# main_board_schem.net
KiCad netlist of a schematic drawn in Altium Designer
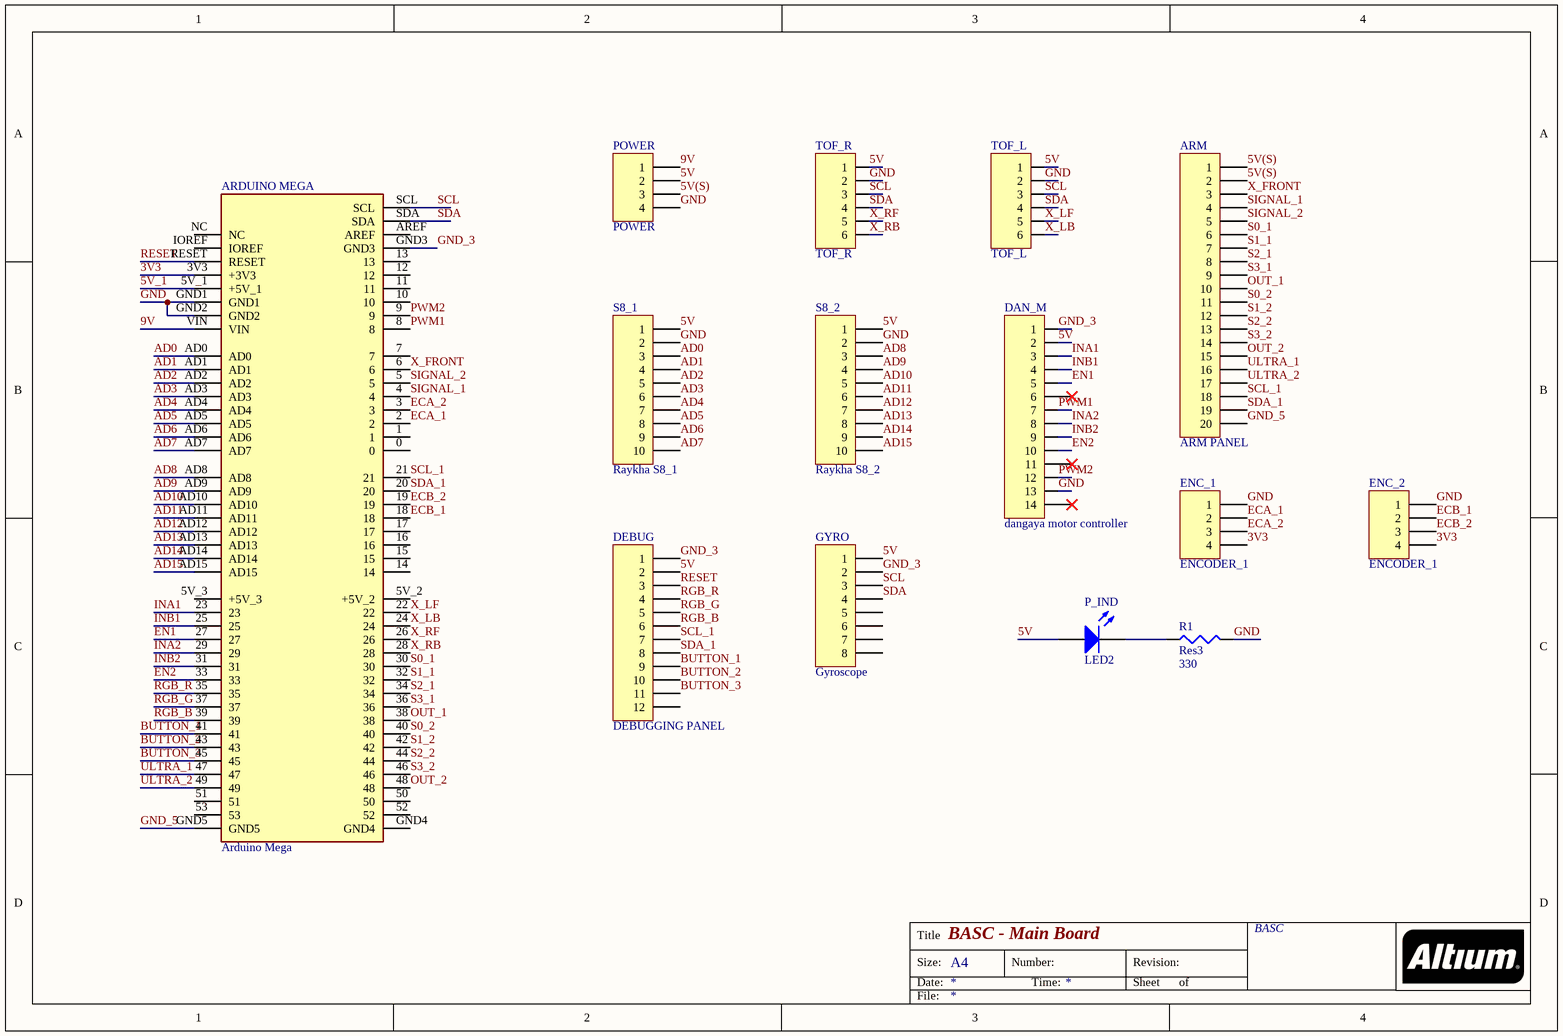
[diagram p0: main_board_schem.SchDoc]

(export (version "E")
  (design (tool "Eeschema 10.0.6"))
  (components
    (comp (ref "ARDUINO MEGA")
      (value "Arduino Mega")
      (footprint "ARDUINO_A000067")
      (description "ATmega2560 Arduino Mega2560 AVRÂ® ATmega AVR MCU 8-Bit Embedded Evaluation Board")
      (fields (field (name "MP") "A000067") (field (name "MF") "Arduino"))
      (libsource (lib "arduino_mega") (part "A000067"))
    )
    (comp (ref "ARM")
      (value "ARM PANEL")
      (footprint "HDR2X10")
      (description "Header, 20-Pin")
      (fields (field (name "PUBLISHER") "Altium Limited"))
      (libsource (lib "Miscellaneous Connectors") (part "Header 20"))
    )
    (comp (ref "DAN_M")
      (value "dangaya motor controller")
      (footprint "HDR1X14")
      (description "Header, 14-Pin")
      (fields (field (name "PUBLISHER") "Altium Limited"))
      (libsource (lib "Miscellaneous Connectors") (part "Header 14"))
    )
    (comp (ref "DEBUG")
      (value "DEBUGGING PANEL")
      (footprint "HDR1X12")
      (description "Header, 12-Pin")
      (fields (field (name "PUBLISHER") "Altium Limited"))
      (libsource (lib "Miscellaneous Connectors") (part "Header 12"))
    )
    (comp (ref "ENC_1")
      (value "ENCODER_1")
      (footprint "HDR1X4")
      (description "Header, 4-Pin")
      (fields (field (name "PUBLISHER") "Altium Limited"))
      (libsource (lib "Miscellaneous Connectors") (part "Header 4"))
    )
    (comp (ref "ENC_2")
      (value "ENCODER_1")
      (footprint "HDR1X4")
      (description "Header, 4-Pin")
      (fields (field (name "PUBLISHER") "Altium Limited"))
      (libsource (lib "Miscellaneous Connectors") (part "Header 4"))
    )
    (comp (ref "GYRO")
      (value "Gyroscope")
      (footprint "HDR1X8")
      (description "Header, 8-Pin")
      (fields (field (name "PUBLISHER") "Altium Limited"))
      (libsource (lib "Miscellaneous Connectors") (part "Header 8"))
    )
    (comp (ref "POWER")
      (value "POWER")
      (footprint "HDR1X4")
      (description "Header, 4-Pin")
      (fields (field (name "PUBLISHER") "Altium Limited"))
      (libsource (lib "Miscellaneous Connectors") (part "Header 4"))
    )
    (comp (ref "P_IND")
      (value "LED2")
      (footprint "3.2X1.6X1.1")
      (description "Typical RED, GREEN, YELLOW, AMBER GaAs LED")
      (fields (field (name "PUBLISHER") "Altium Limited"))
      (libsource (lib "Miscellaneous Devices") (part "LED2"))
    )
    (comp (ref "R1")
      (value "Res3")
      (footprint "RESC3216X75N")
      (description "Resistor")
      (fields (field (name "ALTIUM_VALUE") "330") (field (name "PUBLISHER") "Altium Limited"))
      (libsource (lib "Miscellaneous Devices") (part "Res3"))
    )
    (comp (ref "S8_1")
      (value "Raykha S8_1")
      (footprint "HDR1X10")
      (description "Header, 10-Pin")
      (fields (field (name "PUBLISHER") "Altium Limited"))
      (libsource (lib "Miscellaneous Connectors") (part "Header 10"))
    )
    (comp (ref "S8_2")
      (value "Raykha S8_2")
      (footprint "HDR1X10")
      (description "Header, 10-Pin")
      (fields (field (name "PUBLISHER") "Altium Limited"))
      (libsource (lib "Miscellaneous Connectors") (part "Header 10"))
    )
    (comp (ref "TOF_L")
      (value "TOF_L")
      (footprint "HDR1X6")
      (description "Header, 6-Pin")
      (fields (field (name "PUBLISHER") "Altium Limited"))
      (libsource (lib "Miscellaneous Connectors") (part "Header 6"))
    )
    (comp (ref "TOF_R")
      (value "TOF_R")
      (footprint "HDR1X6")
      (description "Header, 6-Pin")
      (fields (field (name "PUBLISHER") "Altium Limited"))
      (libsource (lib "Miscellaneous Connectors") (part "Header 6"))
    )
  )
  (nets
    (net (code "1") (name "/3V3") (class "Default")
      (node (ref "ARDUINO MEGA") (pin "3V3") (pinfunction "+3V3_3V3") (pintype "passive"))
      (node (ref "ENC_1") (pin "4") (pinfunction "4_4") (pintype "passive"))
      (node (ref "ENC_2") (pin "4") (pinfunction "4_4") (pintype "passive"))
    )
    (net (code "2") (name "/5V") (class "Default")
      (node (ref "DAN_M") (pin "2") (pinfunction "2_2") (pintype "passive"))
      (node (ref "DEBUG") (pin "2") (pinfunction "2_2") (pintype "passive"))
      (node (ref "GYRO") (pin "1") (pinfunction "1_1") (pintype "passive"))
      (node (ref "POWER") (pin "2") (pinfunction "2_2") (pintype "passive"))
      (node (ref "P_IND") (pin "1") (pinfunction "A_1") (pintype "passive"))
      (node (ref "S8_1") (pin "1") (pinfunction "1_1") (pintype "passive"))
      (node (ref "S8_2") (pin "1") (pinfunction "1_1") (pintype "passive"))
      (node (ref "TOF_L") (pin "1") (pinfunction "1_1") (pintype "passive"))
      (node (ref "TOF_R") (pin "1") (pinfunction "1_1") (pintype "passive"))
    )
    (net (code "3") (name "/5V(S)") (class "Default")
      (node (ref "ARM") (pin "1") (pinfunction "1_1") (pintype "passive"))
      (node (ref "ARM") (pin "2") (pinfunction "2_2") (pintype "passive"))
      (node (ref "POWER") (pin "3") (pinfunction "3_3") (pintype "passive"))
    )
    (net (code "4") (name "/5V_1") (class "Default")
      (node (ref "ARDUINO MEGA") (pin "5V_1") (pinfunction "+5V_1_5V_1") (pintype "passive"))
    )
    (net (code "5") (name "/9V") (class "Default")
      (node (ref "ARDUINO MEGA") (pin "VIN") (pinfunction "VIN_VIN") (pintype "passive"))
      (node (ref "POWER") (pin "1") (pinfunction "1_1") (pintype "passive"))
    )
    (net (code "6") (name "/AD0") (class "Default")
      (node (ref "ARDUINO MEGA") (pin "AD0") (pinfunction "AD0_AD0") (pintype "passive"))
      (node (ref "S8_1") (pin "3") (pinfunction "3_3") (pintype "passive"))
    )
    (net (code "7") (name "/AD1") (class "Default")
      (node (ref "ARDUINO MEGA") (pin "AD1") (pinfunction "AD1_AD1") (pintype "passive"))
      (node (ref "S8_1") (pin "4") (pinfunction "4_4") (pintype "passive"))
    )
    (net (code "8") (name "/AD2") (class "Default")
      (node (ref "ARDUINO MEGA") (pin "AD2") (pinfunction "AD2_AD2") (pintype "passive"))
      (node (ref "S8_1") (pin "5") (pinfunction "5_5") (pintype "passive"))
    )
    (net (code "9") (name "/AD3") (class "Default")
      (node (ref "ARDUINO MEGA") (pin "AD3") (pinfunction "AD3_AD3") (pintype "passive"))
      (node (ref "S8_1") (pin "6") (pinfunction "6_6") (pintype "passive"))
    )
    (net (code "10") (name "/AD4") (class "Default")
      (node (ref "ARDUINO MEGA") (pin "AD4") (pinfunction "AD4_AD4") (pintype "passive"))
      (node (ref "S8_1") (pin "7") (pinfunction "7_7") (pintype "passive"))
    )
    (net (code "11") (name "/AD5") (class "Default")
      (node (ref "ARDUINO MEGA") (pin "AD5") (pinfunction "AD5_AD5") (pintype "passive"))
      (node (ref "S8_1") (pin "8") (pinfunction "8_8") (pintype "passive"))
    )
    (net (code "12") (name "/AD6") (class "Default")
      (node (ref "ARDUINO MEGA") (pin "AD6") (pinfunction "AD6_AD6") (pintype "passive"))
      (node (ref "S8_1") (pin "9") (pinfunction "9_9") (pintype "passive"))
    )
    (net (code "13") (name "/AD7") (class "Default")
      (node (ref "ARDUINO MEGA") (pin "AD7") (pinfunction "AD7_AD7") (pintype "passive"))
      (node (ref "S8_1") (pin "10") (pinfunction "10_10") (pintype "passive"))
    )
    (net (code "14") (name "/AD8") (class "Default")
      (node (ref "ARDUINO MEGA") (pin "AD8") (pinfunction "AD8_AD8") (pintype "passive"))
      (node (ref "S8_2") (pin "3") (pinfunction "3_3") (pintype "passive"))
    )
    (net (code "15") (name "/AD9") (class "Default")
      (node (ref "ARDUINO MEGA") (pin "AD9") (pinfunction "AD9_AD9") (pintype "passive"))
      (node (ref "S8_2") (pin "4") (pinfunction "4_4") (pintype "passive"))
    )
    (net (code "16") (name "/AD10") (class "Default")
      (node (ref "ARDUINO MEGA") (pin "AD10") (pinfunction "AD10_AD10") (pintype "passive"))
      (node (ref "S8_2") (pin "5") (pinfunction "5_5") (pintype "passive"))
    )
    (net (code "17") (name "/AD11") (class "Default")
      (node (ref "ARDUINO MEGA") (pin "AD11") (pinfunction "AD11_AD11") (pintype "passive"))
      (node (ref "S8_2") (pin "6") (pinfunction "6_6") (pintype "passive"))
    )
    (net (code "18") (name "/AD12") (class "Default")
      (node (ref "ARDUINO MEGA") (pin "AD12") (pinfunction "AD12_AD12") (pintype "passive"))
      (node (ref "S8_2") (pin "7") (pinfunction "7_7") (pintype "passive"))
    )
    (net (code "19") (name "/AD13") (class "Default")
      (node (ref "ARDUINO MEGA") (pin "AD13") (pinfunction "AD13_AD13") (pintype "passive"))
      (node (ref "S8_2") (pin "8") (pinfunction "8_8") (pintype "passive"))
    )
    (net (code "20") (name "/AD14") (class "Default")
      (node (ref "ARDUINO MEGA") (pin "AD14") (pinfunction "AD14_AD14") (pintype "passive"))
      (node (ref "S8_2") (pin "9") (pinfunction "9_9") (pintype "passive"))
    )
    (net (code "21") (name "/AD15") (class "Default")
      (node (ref "ARDUINO MEGA") (pin "AD15") (pinfunction "AD15_AD15") (pintype "passive"))
      (node (ref "S8_2") (pin "10") (pinfunction "10_10") (pintype "passive"))
    )
    (net (code "22") (name "/BUTTON_1") (class "Default")
      (node (ref "ARDUINO MEGA") (pin "41") (pinfunction "41_41") (pintype "passive"))
      (node (ref "DEBUG") (pin "9") (pinfunction "9_9") (pintype "passive"))
    )
    (net (code "23") (name "/BUTTON_2") (class "Default")
      (node (ref "ARDUINO MEGA") (pin "43") (pinfunction "43_43") (pintype "passive"))
      (node (ref "DEBUG") (pin "10") (pinfunction "10_10") (pintype "passive"))
    )
    (net (code "24") (name "/BUTTON_3") (class "Default")
      (node (ref "ARDUINO MEGA") (pin "45") (pinfunction "45_45") (pintype "passive"))
      (node (ref "DEBUG") (pin "11") (pinfunction "11_11") (pintype "passive"))
    )
    (net (code "25") (name "/ECA_1") (class "Default")
      (node (ref "ARDUINO MEGA") (pin "2") (pinfunction "2_2") (pintype "passive"))
      (node (ref "ENC_1") (pin "2") (pinfunction "2_2") (pintype "passive"))
    )
    (net (code "26") (name "/ECA_2") (class "Default")
      (node (ref "ARDUINO MEGA") (pin "3") (pinfunction "3_3") (pintype "passive"))
      (node (ref "ENC_1") (pin "3") (pinfunction "3_3") (pintype "passive"))
    )
    (net (code "27") (name "/ECB_1") (class "Default")
      (node (ref "ARDUINO MEGA") (pin "18") (pinfunction "18_18") (pintype "passive"))
      (node (ref "ENC_2") (pin "2") (pinfunction "2_2") (pintype "passive"))
    )
    (net (code "28") (name "/ECB_2") (class "Default")
      (node (ref "ARDUINO MEGA") (pin "19") (pinfunction "19_19") (pintype "passive"))
      (node (ref "ENC_2") (pin "3") (pinfunction "3_3") (pintype "passive"))
    )
    (net (code "29") (name "/EN1") (class "Default")
      (node (ref "ARDUINO MEGA") (pin "27") (pinfunction "27_27") (pintype "passive"))
      (node (ref "DAN_M") (pin "5") (pinfunction "5_5") (pintype "passive"))
    )
    (net (code "30") (name "/EN2") (class "Default")
      (node (ref "ARDUINO MEGA") (pin "33") (pinfunction "33_33") (pintype "passive"))
      (node (ref "DAN_M") (pin "10") (pinfunction "10_10") (pintype "passive"))
    )
    (net (code "31") (name "/GND") (class "Default")
      (node (ref "ARDUINO MEGA") (pin "GND1") (pinfunction "GND1_GND1") (pintype "passive"))
      (node (ref "ARDUINO MEGA") (pin "GND2") (pinfunction "GND2_GND2") (pintype "passive"))
      (node (ref "DAN_M") (pin "13") (pinfunction "13_13") (pintype "passive"))
      (node (ref "ENC_1") (pin "1") (pinfunction "1_1") (pintype "passive"))
      (node (ref "ENC_2") (pin "1") (pinfunction "1_1") (pintype "passive"))
      (node (ref "POWER") (pin "4") (pinfunction "4_4") (pintype "passive"))
      (node (ref "R1") (pin "2") (pinfunction "2_2") (pintype "passive"))
      (node (ref "S8_1") (pin "2") (pinfunction "2_2") (pintype "passive"))
      (node (ref "S8_2") (pin "2") (pinfunction "2_2") (pintype "passive"))
      (node (ref "TOF_L") (pin "2") (pinfunction "2_2") (pintype "passive"))
      (node (ref "TOF_R") (pin "2") (pinfunction "2_2") (pintype "passive"))
    )
    (net (code "32") (name "/GND_3") (class "Default")
      (node (ref "ARDUINO MEGA") (pin "GND3") (pinfunction "GND3_GND3") (pintype "passive"))
      (node (ref "DAN_M") (pin "1") (pinfunction "1_1") (pintype "passive"))
      (node (ref "DEBUG") (pin "1") (pinfunction "1_1") (pintype "passive"))
      (node (ref "GYRO") (pin "2") (pinfunction "2_2") (pintype "passive"))
    )
    (net (code "33") (name "/GND_5") (class "Default")
      (node (ref "ARDUINO MEGA") (pin "GND5") (pinfunction "GND5_GND5") (pintype "passive"))
      (node (ref "ARM") (pin "20") (pinfunction "20_20") (pintype "passive"))
    )
    (net (code "34") (name "/INA1") (class "Default")
      (node (ref "ARDUINO MEGA") (pin "23") (pinfunction "23_23") (pintype "passive"))
      (node (ref "DAN_M") (pin "3") (pinfunction "3_3") (pintype "passive"))
    )
    (net (code "35") (name "/INA2") (class "Default")
      (node (ref "ARDUINO MEGA") (pin "29") (pinfunction "29_29") (pintype "passive"))
      (node (ref "DAN_M") (pin "8") (pinfunction "8_8") (pintype "passive"))
    )
    (net (code "36") (name "/INB1") (class "Default")
      (node (ref "ARDUINO MEGA") (pin "25") (pinfunction "25_25") (pintype "passive"))
      (node (ref "DAN_M") (pin "4") (pinfunction "4_4") (pintype "passive"))
    )
    (net (code "37") (name "/INB2") (class "Default")
      (node (ref "ARDUINO MEGA") (pin "31") (pinfunction "31_31") (pintype "passive"))
      (node (ref "DAN_M") (pin "9") (pinfunction "9_9") (pintype "passive"))
    )
    (net (code "38") (name "/OUT_1") (class "Default")
      (node (ref "ARDUINO MEGA") (pin "38") (pinfunction "38_38") (pintype "passive"))
      (node (ref "ARM") (pin "10") (pinfunction "10_10") (pintype "passive"))
    )
    (net (code "39") (name "/OUT_2") (class "Default")
      (node (ref "ARDUINO MEGA") (pin "48") (pinfunction "48_48") (pintype "passive"))
      (node (ref "ARM") (pin "15") (pinfunction "15_15") (pintype "passive"))
    )
    (net (code "40") (name "/PWM1") (class "Default")
      (node (ref "ARDUINO MEGA") (pin "8") (pinfunction "8_8") (pintype "passive"))
      (node (ref "DAN_M") (pin "7") (pinfunction "7_7") (pintype "passive"))
    )
    (net (code "41") (name "/PWM2") (class "Default")
      (node (ref "ARDUINO MEGA") (pin "9") (pinfunction "9_9") (pintype "passive"))
      (node (ref "DAN_M") (pin "12") (pinfunction "12_12") (pintype "passive"))
    )
    (net (code "42") (name "/RESET") (class "Default")
      (node (ref "ARDUINO MEGA") (pin "RESET") (pinfunction "RESET_RESET") (pintype "passive"))
      (node (ref "DEBUG") (pin "3") (pinfunction "3_3") (pintype "passive"))
    )
    (net (code "43") (name "/RGB_B") (class "Default")
      (node (ref "ARDUINO MEGA") (pin "39") (pinfunction "39_39") (pintype "passive"))
      (node (ref "DEBUG") (pin "6") (pinfunction "6_6") (pintype "passive"))
    )
    (net (code "44") (name "/RGB_G") (class "Default")
      (node (ref "ARDUINO MEGA") (pin "37") (pinfunction "37_37") (pintype "passive"))
      (node (ref "DEBUG") (pin "5") (pinfunction "5_5") (pintype "passive"))
    )
    (net (code "45") (name "/RGB_R") (class "Default")
      (node (ref "ARDUINO MEGA") (pin "35") (pinfunction "35_35") (pintype "passive"))
      (node (ref "DEBUG") (pin "4") (pinfunction "4_4") (pintype "passive"))
    )
    (net (code "46") (name "/S0_1") (class "Default")
      (node (ref "ARDUINO MEGA") (pin "30") (pinfunction "30_30") (pintype "passive"))
      (node (ref "ARM") (pin "6") (pinfunction "6_6") (pintype "passive"))
    )
    (net (code "47") (name "/S0_2") (class "Default")
      (node (ref "ARDUINO MEGA") (pin "40") (pinfunction "40_40") (pintype "passive"))
      (node (ref "ARM") (pin "11") (pinfunction "11_11") (pintype "passive"))
    )
    (net (code "48") (name "/S1_1") (class "Default")
      (node (ref "ARDUINO MEGA") (pin "32") (pinfunction "32_32") (pintype "passive"))
      (node (ref "ARM") (pin "7") (pinfunction "7_7") (pintype "passive"))
    )
    (net (code "49") (name "/S1_2") (class "Default")
      (node (ref "ARDUINO MEGA") (pin "42") (pinfunction "42_42") (pintype "passive"))
      (node (ref "ARM") (pin "12") (pinfunction "12_12") (pintype "passive"))
    )
    (net (code "50") (name "/S2_1") (class "Default")
      (node (ref "ARDUINO MEGA") (pin "34") (pinfunction "34_34") (pintype "passive"))
      (node (ref "ARM") (pin "8") (pinfunction "8_8") (pintype "passive"))
    )
    (net (code "51") (name "/S2_2") (class "Default")
      (node (ref "ARDUINO MEGA") (pin "44") (pinfunction "44_44") (pintype "passive"))
      (node (ref "ARM") (pin "13") (pinfunction "13_13") (pintype "passive"))
    )
    (net (code "52") (name "/S3_1") (class "Default")
      (node (ref "ARDUINO MEGA") (pin "36") (pinfunction "36_36") (pintype "passive"))
      (node (ref "ARM") (pin "9") (pinfunction "9_9") (pintype "passive"))
    )
    (net (code "53") (name "/S3_2") (class "Default")
      (node (ref "ARDUINO MEGA") (pin "46") (pinfunction "46_46") (pintype "passive"))
      (node (ref "ARM") (pin "14") (pinfunction "14_14") (pintype "passive"))
    )
    (net (code "54") (name "/SCL") (class "Default")
      (node (ref "ARDUINO MEGA") (pin "SCL") (pinfunction "SCL_SCL") (pintype "passive"))
      (node (ref "GYRO") (pin "3") (pinfunction "3_3") (pintype "passive"))
      (node (ref "TOF_L") (pin "3") (pinfunction "3_3") (pintype "passive"))
      (node (ref "TOF_R") (pin "3") (pinfunction "3_3") (pintype "passive"))
    )
    (net (code "55") (name "/SCL_1") (class "Default")
      (node (ref "ARDUINO MEGA") (pin "21") (pinfunction "21_21") (pintype "passive"))
      (node (ref "ARM") (pin "18") (pinfunction "18_18") (pintype "passive"))
      (node (ref "DEBUG") (pin "7") (pinfunction "7_7") (pintype "passive"))
    )
    (net (code "56") (name "/SDA") (class "Default")
      (node (ref "ARDUINO MEGA") (pin "SDA") (pinfunction "SDA_SDA") (pintype "passive"))
      (node (ref "GYRO") (pin "4") (pinfunction "4_4") (pintype "passive"))
      (node (ref "TOF_L") (pin "4") (pinfunction "4_4") (pintype "passive"))
      (node (ref "TOF_R") (pin "4") (pinfunction "4_4") (pintype "passive"))
    )
    (net (code "57") (name "/SDA_1") (class "Default")
      (node (ref "ARDUINO MEGA") (pin "20") (pinfunction "20_20") (pintype "passive"))
      (node (ref "ARM") (pin "19") (pinfunction "19_19") (pintype "passive"))
      (node (ref "DEBUG") (pin "8") (pinfunction "8_8") (pintype "passive"))
    )
    (net (code "58") (name "/SIGNAL_1") (class "Default")
      (node (ref "ARDUINO MEGA") (pin "4") (pinfunction "4_4") (pintype "passive"))
      (node (ref "ARM") (pin "4") (pinfunction "4_4") (pintype "passive"))
    )
    (net (code "59") (name "/SIGNAL_2") (class "Default")
      (node (ref "ARDUINO MEGA") (pin "5") (pinfunction "5_5") (pintype "passive"))
      (node (ref "ARM") (pin "5") (pinfunction "5_5") (pintype "passive"))
    )
    (net (code "60") (name "/ULTRA_1") (class "Default")
      (node (ref "ARDUINO MEGA") (pin "47") (pinfunction "47_47") (pintype "passive"))
      (node (ref "ARM") (pin "16") (pinfunction "16_16") (pintype "passive"))
    )
    (net (code "61") (name "/ULTRA_2") (class "Default")
      (node (ref "ARDUINO MEGA") (pin "49") (pinfunction "49_49") (pintype "passive"))
      (node (ref "ARM") (pin "17") (pinfunction "17_17") (pintype "passive"))
    )
    (net (code "62") (name "/X_FRONT") (class "Default")
      (node (ref "ARDUINO MEGA") (pin "6") (pinfunction "6_6") (pintype "passive"))
      (node (ref "ARM") (pin "3") (pinfunction "3_3") (pintype "passive"))
    )
    (net (code "63") (name "/X_LB") (class "Default")
      (node (ref "ARDUINO MEGA") (pin "24") (pinfunction "24_24") (pintype "passive"))
      (node (ref "TOF_L") (pin "6") (pinfunction "6_6") (pintype "passive"))
    )
    (net (code "64") (name "/X_LF") (class "Default")
      (node (ref "ARDUINO MEGA") (pin "22") (pinfunction "22_22") (pintype "passive"))
      (node (ref "TOF_L") (pin "5") (pinfunction "5_5") (pintype "passive"))
    )
    (net (code "65") (name "/X_RB") (class "Default")
      (node (ref "ARDUINO MEGA") (pin "28") (pinfunction "28_28") (pintype "passive"))
      (node (ref "TOF_R") (pin "6") (pinfunction "6_6") (pintype "passive"))
    )
    (net (code "66") (name "/X_RF") (class "Default")
      (node (ref "ARDUINO MEGA") (pin "26") (pinfunction "26_26") (pintype "passive"))
      (node (ref "TOF_R") (pin "5") (pinfunction "5_5") (pintype "passive"))
    )
    (net (code "67") (name "Net-(P_IND-K)") (class "Default")
      (node (ref "P_IND") (pin "2") (pinfunction "K_2") (pintype "passive"))
      (node (ref "R1") (pin "1") (pinfunction "1_1") (pintype "passive"))
    )
    (net (code "68") (name "unconnected-(ARDUINO MEGA-+5V_2-Pad5V_2)") (class "Default")
      (node (ref "ARDUINO MEGA") (pin "5V_2") (pinfunction "+5V_2_5V_2") (pintype "passive"))
    )
    (net (code "69") (name "unconnected-(ARDUINO MEGA-+5V_3-Pad5V_3)") (class "Default")
      (node (ref "ARDUINO MEGA") (pin "5V_3") (pinfunction "+5V_3_5V_3") (pintype "passive"))
    )
    (net (code "70") (name "unconnected-(ARDUINO MEGA-Pad0)") (class "Default")
      (node (ref "ARDUINO MEGA") (pin "0") (pinfunction "0_0") (pintype "passive"))
    )
    (net (code "71") (name "unconnected-(ARDUINO MEGA-Pad1)") (class "Default")
      (node (ref "ARDUINO MEGA") (pin "1") (pinfunction "1_1") (pintype "passive"))
    )
    (net (code "72") (name "unconnected-(ARDUINO MEGA-Pad7)") (class "Default")
      (node (ref "ARDUINO MEGA") (pin "7") (pinfunction "7_7") (pintype "passive"))
    )
    (net (code "73") (name "unconnected-(ARDUINO MEGA-Pad10)") (class "Default")
      (node (ref "ARDUINO MEGA") (pin "10") (pinfunction "10_10") (pintype "passive"))
    )
    (net (code "74") (name "unconnected-(ARDUINO MEGA-Pad11)") (class "Default")
      (node (ref "ARDUINO MEGA") (pin "11") (pinfunction "11_11") (pintype "passive"))
    )
    (net (code "75") (name "unconnected-(ARDUINO MEGA-Pad12)") (class "Default")
      (node (ref "ARDUINO MEGA") (pin "12") (pinfunction "12_12") (pintype "passive"))
    )
    (net (code "76") (name "unconnected-(ARDUINO MEGA-Pad13)") (class "Default")
      (node (ref "ARDUINO MEGA") (pin "13") (pinfunction "13_13") (pintype "passive"))
    )
    (net (code "77") (name "unconnected-(ARDUINO MEGA-Pad14)") (class "Default")
      (node (ref "ARDUINO MEGA") (pin "14") (pinfunction "14_14") (pintype "passive"))
    )
    (net (code "78") (name "unconnected-(ARDUINO MEGA-Pad15)") (class "Default")
      (node (ref "ARDUINO MEGA") (pin "15") (pinfunction "15_15") (pintype "passive"))
    )
    (net (code "79") (name "unconnected-(ARDUINO MEGA-Pad16)") (class "Default")
      (node (ref "ARDUINO MEGA") (pin "16") (pinfunction "16_16") (pintype "passive"))
    )
    (net (code "80") (name "unconnected-(ARDUINO MEGA-Pad17)") (class "Default")
      (node (ref "ARDUINO MEGA") (pin "17") (pinfunction "17_17") (pintype "passive"))
    )
    (net (code "81") (name "unconnected-(ARDUINO MEGA-Pad50)") (class "Default")
      (node (ref "ARDUINO MEGA") (pin "50") (pinfunction "50_50") (pintype "passive"))
    )
    (net (code "82") (name "unconnected-(ARDUINO MEGA-Pad51)") (class "Default")
      (node (ref "ARDUINO MEGA") (pin "51") (pinfunction "51_51") (pintype "passive"))
    )
    (net (code "83") (name "unconnected-(ARDUINO MEGA-Pad52)") (class "Default")
      (node (ref "ARDUINO MEGA") (pin "52") (pinfunction "52_52") (pintype "passive"))
    )
    (net (code "84") (name "unconnected-(ARDUINO MEGA-Pad53)") (class "Default")
      (node (ref "ARDUINO MEGA") (pin "53") (pinfunction "53_53") (pintype "passive"))
    )
    (net (code "85") (name "unconnected-(ARDUINO MEGA-PadAREF)") (class "Default")
      (node (ref "ARDUINO MEGA") (pin "AREF") (pinfunction "AREF_AREF") (pintype "passive"))
    )
    (net (code "86") (name "unconnected-(ARDUINO MEGA-PadGND4)") (class "Default")
      (node (ref "ARDUINO MEGA") (pin "GND4") (pinfunction "GND4_GND4") (pintype "passive"))
    )
    (net (code "87") (name "unconnected-(ARDUINO MEGA-PadIOREF)") (class "Default")
      (node (ref "ARDUINO MEGA") (pin "IOREF") (pinfunction "IOREF_IOREF") (pintype "passive"))
    )
    (net (code "88") (name "unconnected-(ARDUINO MEGA-PadNC)") (class "Default")
      (node (ref "ARDUINO MEGA") (pin "NC") (pinfunction "NC_NC") (pintype "passive"))
    )
    (net (code "89") (name "unconnected-(DAN_M-Pad6)") (class "Default")
      (node (ref "DAN_M") (pin "6") (pinfunction "6_6") (pintype "passive+no_connect"))
    )
    (net (code "90") (name "unconnected-(DAN_M-Pad11)") (class "Default")
      (node (ref "DAN_M") (pin "11") (pinfunction "11_11") (pintype "passive+no_connect"))
    )
    (net (code "91") (name "unconnected-(DAN_M-Pad14)") (class "Default")
      (node (ref "DAN_M") (pin "14") (pinfunction "14_14") (pintype "passive+no_connect"))
    )
    (net (code "92") (name "unconnected-(DEBUG-Pad12)") (class "Default")
      (node (ref "DEBUG") (pin "12") (pinfunction "12_12") (pintype "passive"))
    )
    (net (code "93") (name "unconnected-(GYRO-Pad5)") (class "Default")
      (node (ref "GYRO") (pin "5") (pinfunction "5_5") (pintype "passive"))
    )
    (net (code "94") (name "unconnected-(GYRO-Pad6)") (class "Default")
      (node (ref "GYRO") (pin "6") (pinfunction "6_6") (pintype "passive"))
    )
    (net (code "95") (name "unconnected-(GYRO-Pad7)") (class "Default")
      (node (ref "GYRO") (pin "7") (pinfunction "7_7") (pintype "passive"))
    )
    (net (code "96") (name "unconnected-(GYRO-Pad8)") (class "Default")
      (node (ref "GYRO") (pin "8") (pinfunction "8_8") (pintype "passive"))
    )
  )
)
